# telemetrics.net
KiCad netlist of a schematic drawn in EAGLE
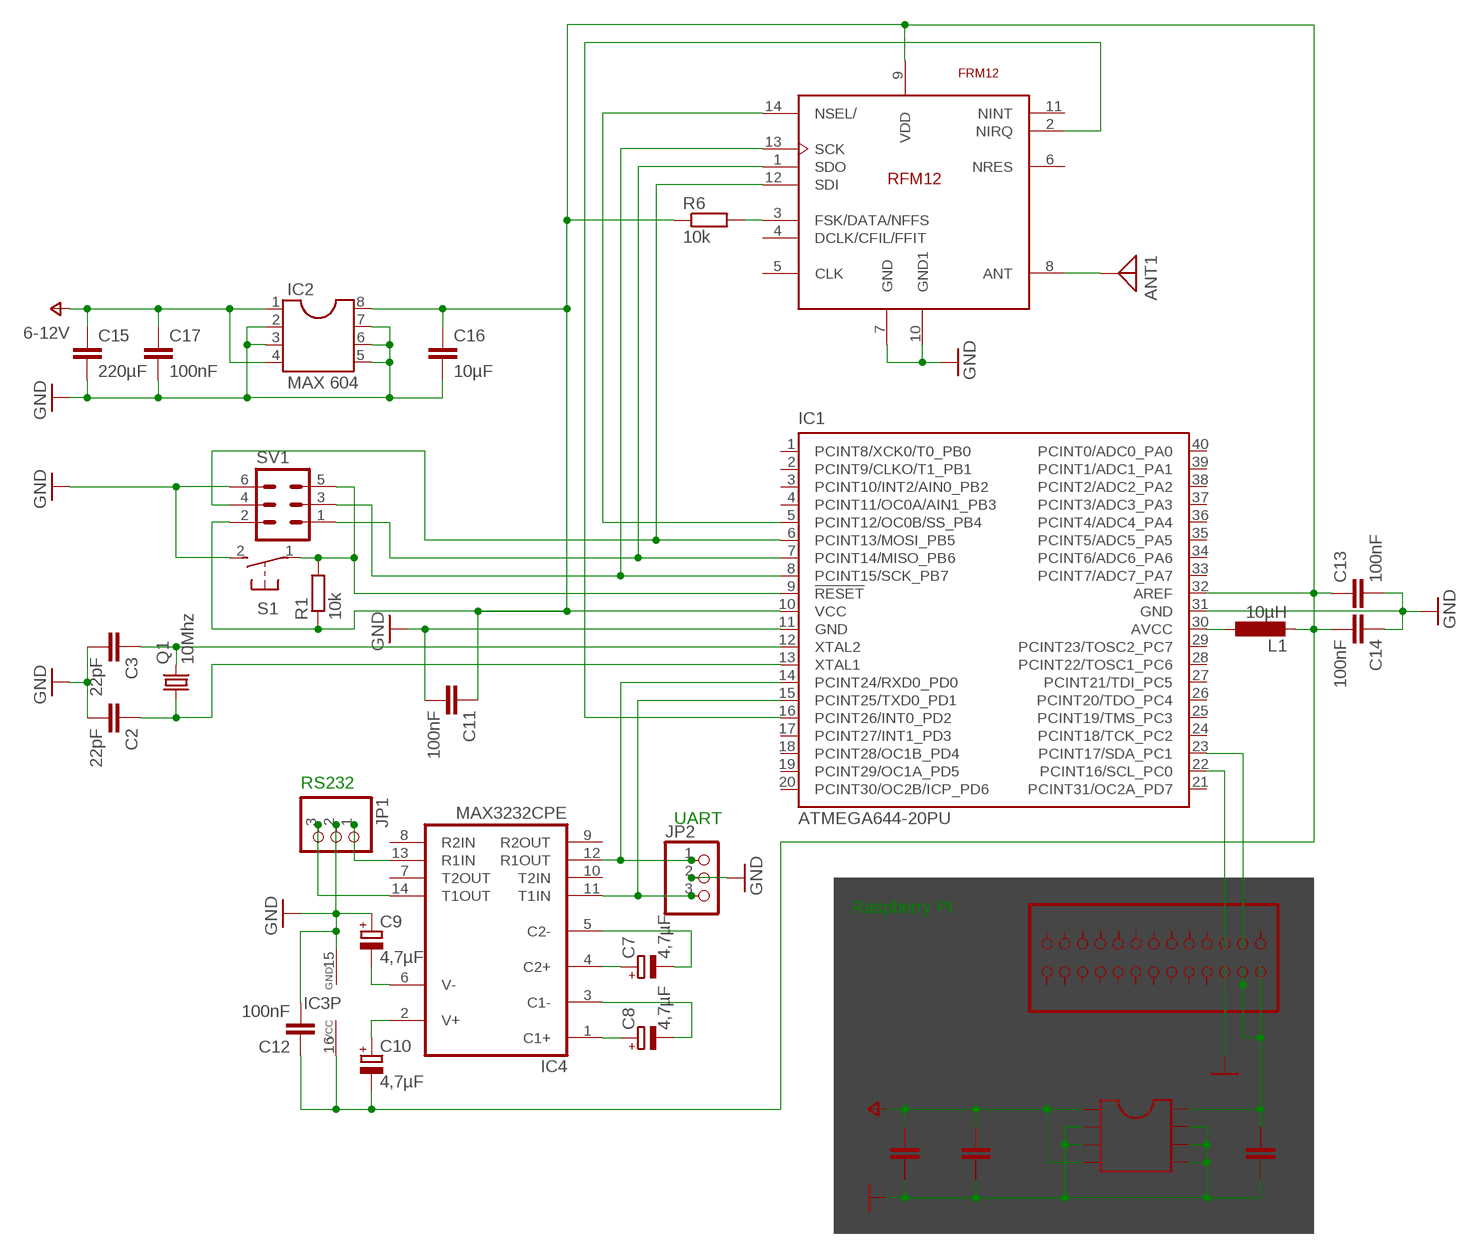
[diagram p0: schematic, sheet 1]

(export (version "E")
  (design (tool "Eeschema 10.0.6"))
  (components
    (comp (ref "ANT1")
      (value "ANTENNA")
      (footprint "eagle-import:PAD-01")
      (libsource (lib "eagle-import") (part "ANTENNA"))
    )
    (comp (ref "C1")
      (value "220µF")
      (footprint "eagle-import:C2.5-6")
      (libsource (lib "eagle-import") (part "C2.5/6"))
    )
    (comp (ref "C2")
      (value "22pF")
      (footprint "eagle-import:C2.5-6")
      (libsource (lib "eagle-import") (part "C2.5/6"))
    )
    (comp (ref "C3")
      (value "22pF")
      (footprint "eagle-import:C2.5-6")
      (libsource (lib "eagle-import") (part "C2.5/6"))
    )
    (comp (ref "C4")
      (value "10µF")
      (footprint "eagle-import:C2.5-5")
      (libsource (lib "eagle-import") (part "C2.5/5"))
    )
    (comp (ref "C5")
      (value "100nF")
      (footprint "eagle-import:C2.5-2")
      (libsource (lib "eagle-import") (part "C2.5/2"))
    )
    (comp (ref "C7")
      (value "4,7µF")
      (footprint "eagle-import:E2,5-6E")
      (libsource (lib "eagle-import") (part "CPOL-EUE2,5-6E"))
    )
    (comp (ref "C8")
      (value "4,7µF")
      (footprint "eagle-import:E2,5-6E")
      (libsource (lib "eagle-import") (part "CPOL-EUE2,5-6E"))
    )
    (comp (ref "C9")
      (value "4,7µF")
      (footprint "eagle-import:E2,5-6E")
      (libsource (lib "eagle-import") (part "CPOL-EUE2,5-6E"))
    )
    (comp (ref "C10")
      (value "4,7µF")
      (footprint "eagle-import:E2,5-6E")
      (libsource (lib "eagle-import") (part "CPOL-EUE2,5-6E"))
    )
    (comp (ref "C11")
      (value "100nF")
      (footprint "eagle-import:C2.5-6")
      (libsource (lib "eagle-import") (part "C2.5/6"))
    )
    (comp (ref "C12")
      (value "100nF")
      (footprint "eagle-import:C2.5-6")
      (libsource (lib "eagle-import") (part "C2.5/6"))
    )
    (comp (ref "C13")
      (value "100nF")
      (footprint "eagle-import:C2.5-6")
      (libsource (lib "eagle-import") (part "C2.5/6"))
    )
    (comp (ref "C14")
      (value "100nF")
      (footprint "eagle-import:C2.5-6")
      (libsource (lib "eagle-import") (part "C2.5/6"))
    )
    (comp (ref "C15")
      (value "220µF")
      (footprint "eagle-import:C2.5-6")
      (libsource (lib "eagle-import") (part "C2.5/6"))
    )
    (comp (ref "C16")
      (value "10µF")
      (footprint "eagle-import:C2.5-5")
      (libsource (lib "eagle-import") (part "C2.5/5"))
    )
    (comp (ref "C17")
      (value "100nF")
      (footprint "eagle-import:C2.5-2")
      (libsource (lib "eagle-import") (part "C2.5/2"))
    )
    (comp (ref "IC1")
      (value "ATMEGA644-20PU")
      (footprint "eagle-import:DIL40")
      (libsource (lib "eagle-import") (part "ATMEGA644-PU20"))
    )
    (comp (ref "IC2")
      (value "MAX 604")
      (footprint "eagle-import:SOCKET-08")
      (libsource (lib "eagle-import") (part "DIL8S"))
    )
    (comp (ref "IC3")
      (value "MAX232")
      (footprint "eagle-import:DIL16")
      (fields (field (name "MF") "MAXIM") (field (name "MPN") "MAX232ACPE+"))
      (libsource (lib "eagle-import") (part "MAX232"))
    )
    (comp (ref "IC4")
      (value "MAX3232CPE")
      (footprint "eagle-import:DIL16")
      (fields (field (name "MF") "MAXIM") (field (name "MPN") "MAX3232CPE+"))
      (libsource (lib "eagle-import") (part "MAX3232PEC"))
    )
    (comp (ref "IC5")
      (value "MAX 603")
      (footprint "eagle-import:SOCKET-08")
      (libsource (lib "eagle-import") (part "DIL8S"))
    )
    (comp (ref "JP1")
      (value "PINHD-1X3")
      (footprint "eagle-import:1X03")
      (libsource (lib "eagle-import") (part "PINHD-1X3"))
    )
    (comp (ref "JP2")
      (value "PINHD-1X3")
      (footprint "eagle-import:1X03")
      (libsource (lib "eagle-import") (part "PINHD-1X3"))
    )
    (comp (ref "JP3")
      (value "Raspberry GPIO")
      (footprint "eagle-import:2X13")
      (libsource (lib "eagle-import") (part "PINHD-2X13"))
    )
    (comp (ref "L1")
      (value "10µH")
      (footprint "eagle-import:IRF-3")
      (libsource (lib "eagle-import") (part "L-EUIRF-3"))
    )
    (comp (ref "Q1")
      (value "10Mhz")
      (footprint "eagle-import:HC49U70")
      (libsource (lib "eagle-import") (part "CRYSTALHC49U70"))
    )
    (comp (ref "R1")
      (value "10k")
      (footprint "eagle-import:0207_10")
      (libsource (lib "eagle-import") (part "R-EU_0207/10"))
    )
    (comp (ref "R6")
      (value "10k")
      (footprint "eagle-import:0207_10")
      (libsource (lib "eagle-import") (part "R-EU_0207/10"))
    )
    (comp (ref "S1")
      (value "31-XX")
      (footprint "eagle-import:B3F-31XX")
      (fields (field (name "MPN") "B3F-3100"))
      (libsource (lib "eagle-import") (part "31-XX"))
    )
    (comp (ref "SV1")
      (value "ML6")
      (footprint "eagle-import:ML6")
      (libsource (lib "eagle-import") (part "ML6"))
    )
    (comp (ref "U$2")
      (value "FRM12")
      (footprint "eagle-import:RFM12")
      (libsource (lib "eagle-import") (part "FRM12"))
    )
  )
  (nets
    (net (code "1") (name "6-12V") (class "Default")
      (node (ref "C1") (pin "1") (pinfunction "1_1") (pintype "passive"))
      (node (ref "C15") (pin "1") (pinfunction "1_1") (pintype "passive"))
      (node (ref "C17") (pin "1") (pinfunction "1_1") (pintype "passive"))
      (node (ref "C5") (pin "1") (pinfunction "1_1") (pintype "passive"))
      (node (ref "IC2") (pin "1") (pinfunction "1_1") (pintype "passive"))
      (node (ref "IC2") (pin "4") (pinfunction "4_4") (pintype "passive"))
      (node (ref "IC5") (pin "1") (pinfunction "1_1") (pintype "passive"))
      (node (ref "IC5") (pin "4") (pinfunction "4_4") (pintype "passive"))
    )
    (net (code "2") (name "GND") (class "Default")
      (node (ref "C1") (pin "2") (pinfunction "2_2") (pintype "passive"))
      (node (ref "C11") (pin "2") (pinfunction "2_2") (pintype "passive"))
      (node (ref "C12") (pin "2") (pinfunction "2_2") (pintype "passive"))
      (node (ref "C13") (pin "2") (pinfunction "2_2") (pintype "passive"))
      (node (ref "C14") (pin "1") (pinfunction "1_1") (pintype "passive"))
      (node (ref "C15") (pin "2") (pinfunction "2_2") (pintype "passive"))
      (node (ref "C16") (pin "2") (pinfunction "2_2") (pintype "passive"))
      (node (ref "C17") (pin "2") (pinfunction "2_2") (pintype "passive"))
      (node (ref "C2") (pin "2") (pinfunction "2_2") (pintype "passive"))
      (node (ref "C3") (pin "2") (pinfunction "2_2") (pintype "passive"))
      (node (ref "C4") (pin "2") (pinfunction "2_2") (pintype "passive"))
      (node (ref "C5") (pin "2") (pinfunction "2_2") (pintype "passive"))
      (node (ref "C9") (pin "+") (pinfunction "+_+") (pintype "passive"))
      (node (ref "IC1") (pin "11") (pinfunction "GND_11") (pintype "power_in"))
      (node (ref "IC1") (pin "31") (pinfunction "GND_31") (pintype "power_in"))
      (node (ref "IC2") (pin "2") (pinfunction "2_2") (pintype "passive"))
      (node (ref "IC2") (pin "3") (pinfunction "3_3") (pintype "passive"))
      (node (ref "IC2") (pin "5") (pinfunction "5_5") (pintype "passive"))
      (node (ref "IC2") (pin "6") (pinfunction "6_6") (pintype "passive"))
      (node (ref "IC2") (pin "7") (pinfunction "7_7") (pintype "passive"))
      (node (ref "IC3") (pin "15") (pinfunction "GND_15") (pintype "power_in"))
      (node (ref "IC5") (pin "2") (pinfunction "2_2") (pintype "passive"))
      (node (ref "IC5") (pin "3") (pinfunction "3_3") (pintype "passive"))
      (node (ref "IC5") (pin "5") (pinfunction "5_5") (pintype "passive"))
      (node (ref "IC5") (pin "6") (pinfunction "6_6") (pintype "passive"))
      (node (ref "IC5") (pin "7") (pinfunction "7_7") (pintype "passive"))
      (node (ref "JP1") (pin "2") (pinfunction "2_2") (pintype "passive"))
      (node (ref "JP2") (pin "2") (pinfunction "2_2") (pintype "passive"))
      (node (ref "JP3") (pin "6") (pinfunction "6_6") (pintype "passive"))
      (node (ref "S1") (pin "2") (pinfunction "S_2") (pintype "passive"))
      (node (ref "SV1") (pin "6") (pinfunction "6_6") (pintype "passive"))
      (node (ref "U$2") (pin "10") (pinfunction "GND1_10") (pintype "passive"))
      (node (ref "U$2") (pin "7") (pinfunction "GND_7") (pintype "passive"))
    )
    (net (code "3") (name "Net-(C4-Pad1)") (class "Default")
      (node (ref "C4") (pin "1") (pinfunction "1_1") (pintype "passive"))
      (node (ref "IC5") (pin "8") (pinfunction "8_8") (pintype "passive"))
      (node (ref "JP3") (pin "2") (pinfunction "2_2") (pintype "passive"))
      (node (ref "JP3") (pin "4") (pinfunction "4_4") (pintype "passive"))
    )
    (net (code "4") (name "Net-(IC1-AREF)") (class "Default")
      (node (ref "C10") (pin "-") (pinfunction "-_-") (pintype "passive"))
      (node (ref "C11") (pin "1") (pinfunction "1_1") (pintype "passive"))
      (node (ref "C12") (pin "1") (pinfunction "1_1") (pintype "passive"))
      (node (ref "C13") (pin "1") (pinfunction "1_1") (pintype "passive"))
      (node (ref "C14") (pin "2") (pinfunction "2_2") (pintype "passive"))
      (node (ref "C16") (pin "1") (pinfunction "1_1") (pintype "passive"))
      (node (ref "IC1") (pin "10") (pinfunction "VCC_10") (pintype "power_in"))
      (node (ref "IC1") (pin "32") (pinfunction "AREF_32") (pintype "passive"))
      (node (ref "IC2") (pin "8") (pinfunction "8_8") (pintype "passive"))
      (node (ref "IC3") (pin "16") (pinfunction "VCC_16") (pintype "power_in"))
      (node (ref "L1") (pin "2") (pinfunction "2_2") (pintype "passive"))
      (node (ref "R1") (pin "1") (pinfunction "1_1") (pintype "passive"))
      (node (ref "R6") (pin "1") (pinfunction "1_1") (pintype "passive"))
      (node (ref "SV1") (pin "2") (pinfunction "2_2") (pintype "passive"))
      (node (ref "U$2") (pin "9") (pinfunction "VDD_9") (pintype "power_in"))
    )
    (net (code "5") (name "Net-(IC1-AVCC)") (class "Default")
      (node (ref "IC1") (pin "30") (pinfunction "AVCC_30") (pintype "power_in"))
      (node (ref "L1") (pin "1") (pinfunction "1_1") (pintype "passive"))
    )
    (net (code "6") (name "Net-(IC1-PCINT12{slash}OC0B{slash}SS_PB4)") (class "Default")
      (node (ref "IC1") (pin "5") (pinfunction "PCINT12/OC0B/SS_PB4_5") (pintype "bidirectional"))
      (node (ref "U$2") (pin "14") (pinfunction "NSEL/_14") (pintype "input"))
    )
    (net (code "7") (name "Net-(IC1-PCINT13{slash}MOSI_PB5)") (class "Default")
      (node (ref "IC1") (pin "6") (pinfunction "PCINT13/MOSI_PB5_6") (pintype "bidirectional"))
      (node (ref "SV1") (pin "4") (pinfunction "4_4") (pintype "passive"))
      (node (ref "U$2") (pin "12") (pinfunction "SDI_12") (pintype "input"))
    )
    (net (code "8") (name "Net-(IC1-PCINT14{slash}MISO_PB6)") (class "Default")
      (node (ref "IC1") (pin "7") (pinfunction "PCINT14/MISO_PB6_7") (pintype "bidirectional"))
      (node (ref "SV1") (pin "1") (pinfunction "1_1") (pintype "passive"))
      (node (ref "U$2") (pin "1") (pinfunction "SDO_1") (pintype "output"))
    )
    (net (code "9") (name "Net-(IC1-PCINT15{slash}SCK_PB7)") (class "Default")
      (node (ref "IC1") (pin "8") (pinfunction "PCINT15/SCK_PB7_8") (pintype "bidirectional"))
      (node (ref "SV1") (pin "3") (pinfunction "3_3") (pintype "passive"))
      (node (ref "U$2") (pin "13") (pinfunction "SCK_13") (pintype "input"))
    )
    (net (code "10") (name "Net-(IC1-PCINT16{slash}SCL_PC0)") (class "Default")
      (node (ref "IC1") (pin "22") (pinfunction "PCINT16/SCL_PC0_22") (pintype "bidirectional"))
      (node (ref "JP3") (pin "5") (pinfunction "5_5") (pintype "passive"))
    )
    (net (code "11") (name "Net-(IC1-PCINT17{slash}SDA_PC1)") (class "Default")
      (node (ref "IC1") (pin "23") (pinfunction "PCINT17/SDA_PC1_23") (pintype "bidirectional"))
      (node (ref "JP3") (pin "3") (pinfunction "3_3") (pintype "passive"))
    )
    (net (code "12") (name "Net-(IC1-PCINT24{slash}RXD0_PD0)") (class "Default")
      (node (ref "IC1") (pin "14") (pinfunction "PCINT24/RXD0_PD0_14") (pintype "bidirectional"))
      (node (ref "IC4") (pin "12") (pinfunction "R1OUT_12") (pintype "output"))
      (node (ref "JP2") (pin "1") (pinfunction "1_1") (pintype "passive"))
    )
    (net (code "13") (name "Net-(IC1-PCINT25{slash}TXD0_PD1)") (class "Default")
      (node (ref "IC1") (pin "15") (pinfunction "PCINT25/TXD0_PD1_15") (pintype "bidirectional"))
      (node (ref "IC4") (pin "11") (pinfunction "T1IN_11") (pintype "input"))
      (node (ref "JP2") (pin "3") (pinfunction "3_3") (pintype "passive"))
    )
    (net (code "14") (name "Net-(IC1-PCINT26{slash}INT0_PD2)") (class "Default")
      (node (ref "IC1") (pin "16") (pinfunction "PCINT26/INT0_PD2_16") (pintype "bidirectional"))
      (node (ref "U$2") (pin "2") (pinfunction "NIRQ_2") (pintype "output"))
    )
    (net (code "15") (name "Net-(IC1-XTAL1)") (class "Default")
      (node (ref "C2") (pin "1") (pinfunction "1_1") (pintype "passive"))
      (node (ref "IC1") (pin "13") (pinfunction "XTAL1_13") (pintype "input"))
      (node (ref "Q1") (pin "1") (pinfunction "1_1") (pintype "passive"))
    )
    (net (code "16") (name "Net-(IC1-XTAL2)") (class "Default")
      (node (ref "C3") (pin "1") (pinfunction "1_1") (pintype "passive"))
      (node (ref "IC1") (pin "12") (pinfunction "XTAL2_12") (pintype "output"))
      (node (ref "Q1") (pin "2") (pinfunction "2_2") (pintype "passive"))
    )
    (net (code "17") (name "Net-(IC1-~{RESET})") (class "Default")
      (node (ref "IC1") (pin "9") (pinfunction "~{RESET}_9") (pintype "input"))
      (node (ref "R1") (pin "2") (pinfunction "2_2") (pintype "passive"))
      (node (ref "S1") (pin "1") (pinfunction "P_1") (pintype "passive"))
      (node (ref "SV1") (pin "5") (pinfunction "5_5") (pintype "passive"))
    )
    (net (code "18") (name "Net-(IC4A-C1+)") (class "Default")
      (node (ref "C8") (pin "+") (pinfunction "+_+") (pintype "passive"))
      (node (ref "IC4") (pin "1") (pinfunction "C1+_1") (pintype "bidirectional"))
    )
    (net (code "19") (name "Net-(IC4A-C1-)") (class "Default")
      (node (ref "C8") (pin "-") (pinfunction "-_-") (pintype "passive"))
      (node (ref "IC4") (pin "3") (pinfunction "C1-_3") (pintype "bidirectional"))
    )
    (net (code "20") (name "Net-(IC4A-C2+)") (class "Default")
      (node (ref "C7") (pin "+") (pinfunction "+_+") (pintype "passive"))
      (node (ref "IC4") (pin "4") (pinfunction "C2+_4") (pintype "bidirectional"))
    )
    (net (code "21") (name "Net-(IC4A-C2-)") (class "Default")
      (node (ref "C7") (pin "-") (pinfunction "-_-") (pintype "passive"))
      (node (ref "IC4") (pin "5") (pinfunction "C2-_5") (pintype "bidirectional"))
    )
    (net (code "22") (name "Net-(IC4A-R1IN)") (class "Default")
      (node (ref "IC4") (pin "13") (pinfunction "R1IN_13") (pintype "input"))
      (node (ref "JP1") (pin "1") (pinfunction "1_1") (pintype "passive"))
    )
    (net (code "23") (name "Net-(IC4A-T1OUT)") (class "Default")
      (node (ref "IC4") (pin "14") (pinfunction "T1OUT_14") (pintype "output"))
      (node (ref "JP1") (pin "3") (pinfunction "3_3") (pintype "passive"))
    )
    (net (code "24") (name "Net-(IC4A-V+)") (class "Default")
      (node (ref "C10") (pin "+") (pinfunction "+_+") (pintype "passive"))
      (node (ref "IC4") (pin "2") (pinfunction "V+_2") (pintype "bidirectional"))
    )
    (net (code "25") (name "Net-(IC4A-V-)") (class "Default")
      (node (ref "C9") (pin "-") (pinfunction "-_-") (pintype "passive"))
      (node (ref "IC4") (pin "6") (pinfunction "V-_6") (pintype "bidirectional"))
    )
    (net (code "26") (name "Net-(U$2-ANT)") (class "Default")
      (node (ref "ANT1") (pin "1") (pinfunction "1_1") (pintype "output"))
      (node (ref "U$2") (pin "8") (pinfunction "ANT_8") (pintype "bidirectional"))
    )
    (net (code "27") (name "Net-(U$2-FSK{slash}DATA{slash}NFFS)") (class "Default")
      (node (ref "R6") (pin "2") (pinfunction "2_2") (pintype "passive"))
      (node (ref "U$2") (pin "3") (pinfunction "FSK/DATA/NFFS_3") (pintype "bidirectional"))
    )
    (net (code "28") (name "unconnected-(IC1-PCINT0{slash}ADC0_PA0-Pad40)") (class "Default")
      (node (ref "IC1") (pin "40") (pinfunction "PCINT0/ADC0_PA0_40") (pintype "bidirectional"))
    )
    (net (code "29") (name "unconnected-(IC1-PCINT1{slash}ADC1_PA1-Pad39)") (class "Default")
      (node (ref "IC1") (pin "39") (pinfunction "PCINT1/ADC1_PA1_39") (pintype "bidirectional"))
    )
    (net (code "30") (name "unconnected-(IC1-PCINT2{slash}ADC2_PA2-Pad38)") (class "Default")
      (node (ref "IC1") (pin "38") (pinfunction "PCINT2/ADC2_PA2_38") (pintype "bidirectional"))
    )
    (net (code "31") (name "unconnected-(IC1-PCINT3{slash}ADC3_PA3-Pad37)") (class "Default")
      (node (ref "IC1") (pin "37") (pinfunction "PCINT3/ADC3_PA3_37") (pintype "bidirectional"))
    )
    (net (code "32") (name "unconnected-(IC1-PCINT4{slash}ADC4_PA4-Pad36)") (class "Default")
      (node (ref "IC1") (pin "36") (pinfunction "PCINT4/ADC4_PA4_36") (pintype "bidirectional"))
    )
    (net (code "33") (name "unconnected-(IC1-PCINT5{slash}ADC5_PA5-Pad35)") (class "Default")
      (node (ref "IC1") (pin "35") (pinfunction "PCINT5/ADC5_PA5_35") (pintype "bidirectional"))
    )
    (net (code "34") (name "unconnected-(IC1-PCINT6{slash}ADC6_PA6-Pad34)") (class "Default")
      (node (ref "IC1") (pin "34") (pinfunction "PCINT6/ADC6_PA6_34") (pintype "bidirectional"))
    )
    (net (code "35") (name "unconnected-(IC1-PCINT7{slash}ADC7_PA7-Pad33)") (class "Default")
      (node (ref "IC1") (pin "33") (pinfunction "PCINT7/ADC7_PA7_33") (pintype "bidirectional"))
    )
    (net (code "36") (name "unconnected-(IC1-PCINT8{slash}XCK0{slash}T0_PB0-Pad1)") (class "Default")
      (node (ref "IC1") (pin "1") (pinfunction "PCINT8/XCK0/T0_PB0_1") (pintype "bidirectional"))
    )
    (net (code "37") (name "unconnected-(IC1-PCINT9{slash}CLKO{slash}T1_PB1-Pad2)") (class "Default")
      (node (ref "IC1") (pin "2") (pinfunction "PCINT9/CLKO/T1_PB1_2") (pintype "bidirectional"))
    )
    (net (code "38") (name "unconnected-(IC1-PCINT10{slash}INT2{slash}AIN0_PB2-Pad3)") (class "Default")
      (node (ref "IC1") (pin "3") (pinfunction "PCINT10/INT2/AIN0_PB2_3") (pintype "bidirectional"))
    )
    (net (code "39") (name "unconnected-(IC1-PCINT11{slash}OC0A{slash}AIN1_PB3-Pad4)") (class "Default")
      (node (ref "IC1") (pin "4") (pinfunction "PCINT11/OC0A/AIN1_PB3_4") (pintype "bidirectional"))
    )
    (net (code "40") (name "unconnected-(IC1-PCINT18{slash}TCK_PC2-Pad24)") (class "Default")
      (node (ref "IC1") (pin "24") (pinfunction "PCINT18/TCK_PC2_24") (pintype "bidirectional"))
    )
    (net (code "41") (name "unconnected-(IC1-PCINT19{slash}TMS_PC3-Pad25)") (class "Default")
      (node (ref "IC1") (pin "25") (pinfunction "PCINT19/TMS_PC3_25") (pintype "bidirectional"))
    )
    (net (code "42") (name "unconnected-(IC1-PCINT20{slash}TDO_PC4-Pad26)") (class "Default")
      (node (ref "IC1") (pin "26") (pinfunction "PCINT20/TDO_PC4_26") (pintype "bidirectional"))
    )
    (net (code "43") (name "unconnected-(IC1-PCINT21{slash}TDI_PC5-Pad27)") (class "Default")
      (node (ref "IC1") (pin "27") (pinfunction "PCINT21/TDI_PC5_27") (pintype "bidirectional"))
    )
    (net (code "44") (name "unconnected-(IC1-PCINT22{slash}TOSC1_PC6-Pad28)") (class "Default")
      (node (ref "IC1") (pin "28") (pinfunction "PCINT22/TOSC1_PC6_28") (pintype "bidirectional"))
    )
    (net (code "45") (name "unconnected-(IC1-PCINT23{slash}TOSC2_PC7-Pad29)") (class "Default")
      (node (ref "IC1") (pin "29") (pinfunction "PCINT23/TOSC2_PC7_29") (pintype "bidirectional"))
    )
    (net (code "46") (name "unconnected-(IC1-PCINT27{slash}INT1_PD3-Pad17)") (class "Default")
      (node (ref "IC1") (pin "17") (pinfunction "PCINT27/INT1_PD3_17") (pintype "bidirectional"))
    )
    (net (code "47") (name "unconnected-(IC1-PCINT28{slash}OC1B_PD4-Pad18)") (class "Default")
      (node (ref "IC1") (pin "18") (pinfunction "PCINT28/OC1B_PD4_18") (pintype "bidirectional"))
    )
    (net (code "48") (name "unconnected-(IC1-PCINT29{slash}OC1A_PD5-Pad19)") (class "Default")
      (node (ref "IC1") (pin "19") (pinfunction "PCINT29/OC1A_PD5_19") (pintype "bidirectional"))
    )
    (net (code "49") (name "unconnected-(IC1-PCINT30{slash}OC2B{slash}ICP_PD6-Pad20)") (class "Default")
      (node (ref "IC1") (pin "20") (pinfunction "PCINT30/OC2B/ICP_PD6_20") (pintype "bidirectional"))
    )
    (net (code "50") (name "unconnected-(IC1-PCINT31{slash}OC2A_PD7-Pad21)") (class "Default")
      (node (ref "IC1") (pin "21") (pinfunction "PCINT31/OC2A_PD7_21") (pintype "bidirectional"))
    )
    (net (code "51") (name "unconnected-(IC4A-R2IN-Pad8)") (class "Default")
      (node (ref "IC4") (pin "8") (pinfunction "R2IN_8") (pintype "input"))
    )
    (net (code "52") (name "unconnected-(IC4A-R2OUT-Pad9)") (class "Default")
      (node (ref "IC4") (pin "9") (pinfunction "R2OUT_9") (pintype "output"))
    )
    (net (code "53") (name "unconnected-(IC4A-T2IN-Pad10)") (class "Default")
      (node (ref "IC4") (pin "10") (pinfunction "T2IN_10") (pintype "input"))
    )
    (net (code "54") (name "unconnected-(IC4A-T2OUT-Pad7)") (class "Default")
      (node (ref "IC4") (pin "7") (pinfunction "T2OUT_7") (pintype "output"))
    )
    (net (code "55") (name "unconnected-(JP3-Pad1)") (class "Default")
      (node (ref "JP3") (pin "1") (pinfunction "1_1") (pintype "passive"))
    )
    (net (code "56") (name "unconnected-(JP3-Pad7)") (class "Default")
      (node (ref "JP3") (pin "7") (pinfunction "7_7") (pintype "passive"))
    )
    (net (code "57") (name "unconnected-(JP3-Pad8)") (class "Default")
      (node (ref "JP3") (pin "8") (pinfunction "8_8") (pintype "passive"))
    )
    (net (code "58") (name "unconnected-(JP3-Pad9)") (class "Default")
      (node (ref "JP3") (pin "9") (pinfunction "9_9") (pintype "passive"))
    )
    (net (code "59") (name "unconnected-(JP3-Pad10)") (class "Default")
      (node (ref "JP3") (pin "10") (pinfunction "10_10") (pintype "passive"))
    )
    (net (code "60") (name "unconnected-(JP3-Pad11)") (class "Default")
      (node (ref "JP3") (pin "11") (pinfunction "11_11") (pintype "passive"))
    )
    (net (code "61") (name "unconnected-(JP3-Pad12)") (class "Default")
      (node (ref "JP3") (pin "12") (pinfunction "12_12") (pintype "passive"))
    )
    (net (code "62") (name "unconnected-(JP3-Pad13)") (class "Default")
      (node (ref "JP3") (pin "13") (pinfunction "13_13") (pintype "passive"))
    )
    (net (code "63") (name "unconnected-(JP3-Pad14)") (class "Default")
      (node (ref "JP3") (pin "14") (pinfunction "14_14") (pintype "passive"))
    )
    (net (code "64") (name "unconnected-(JP3-Pad15)") (class "Default")
      (node (ref "JP3") (pin "15") (pinfunction "15_15") (pintype "passive"))
    )
    (net (code "65") (name "unconnected-(JP3-Pad16)") (class "Default")
      (node (ref "JP3") (pin "16") (pinfunction "16_16") (pintype "passive"))
    )
    (net (code "66") (name "unconnected-(JP3-Pad17)") (class "Default")
      (node (ref "JP3") (pin "17") (pinfunction "17_17") (pintype "passive"))
    )
    (net (code "67") (name "unconnected-(JP3-Pad18)") (class "Default")
      (node (ref "JP3") (pin "18") (pinfunction "18_18") (pintype "passive"))
    )
    (net (code "68") (name "unconnected-(JP3-Pad19)") (class "Default")
      (node (ref "JP3") (pin "19") (pinfunction "19_19") (pintype "passive"))
    )
    (net (code "69") (name "unconnected-(JP3-Pad20)") (class "Default")
      (node (ref "JP3") (pin "20") (pinfunction "20_20") (pintype "passive"))
    )
    (net (code "70") (name "unconnected-(JP3-Pad21)") (class "Default")
      (node (ref "JP3") (pin "21") (pinfunction "21_21") (pintype "passive"))
    )
    (net (code "71") (name "unconnected-(JP3-Pad22)") (class "Default")
      (node (ref "JP3") (pin "22") (pinfunction "22_22") (pintype "passive"))
    )
    (net (code "72") (name "unconnected-(JP3-Pad23)") (class "Default")
      (node (ref "JP3") (pin "23") (pinfunction "23_23") (pintype "passive"))
    )
    (net (code "73") (name "unconnected-(JP3-Pad24)") (class "Default")
      (node (ref "JP3") (pin "24") (pinfunction "24_24") (pintype "passive"))
    )
    (net (code "74") (name "unconnected-(JP3-Pad25)") (class "Default")
      (node (ref "JP3") (pin "25") (pinfunction "25_25") (pintype "passive"))
    )
    (net (code "75") (name "unconnected-(JP3-Pad26)") (class "Default")
      (node (ref "JP3") (pin "26") (pinfunction "26_26") (pintype "passive"))
    )
    (net (code "76") (name "unconnected-(U$2-CLK-Pad5)") (class "Default")
      (node (ref "U$2") (pin "5") (pinfunction "CLK_5") (pintype "output"))
    )
    (net (code "77") (name "unconnected-(U$2-DCLK{slash}CFIL{slash}FFIT-Pad4)") (class "Default")
      (node (ref "U$2") (pin "4") (pinfunction "DCLK/CFIL/FFIT_4") (pintype "bidirectional"))
    )
    (net (code "78") (name "unconnected-(U$2-NINT-Pad11)") (class "Default")
      (node (ref "U$2") (pin "11") (pinfunction "NINT_11") (pintype "bidirectional"))
    )
    (net (code "79") (name "unconnected-(U$2-NRES-Pad6)") (class "Default")
      (node (ref "U$2") (pin "6") (pinfunction "NRES_6") (pintype "bidirectional"))
    )
  )
)
